# user_control_design_block.net
KiCad netlist of a schematic drawn in EAGLE
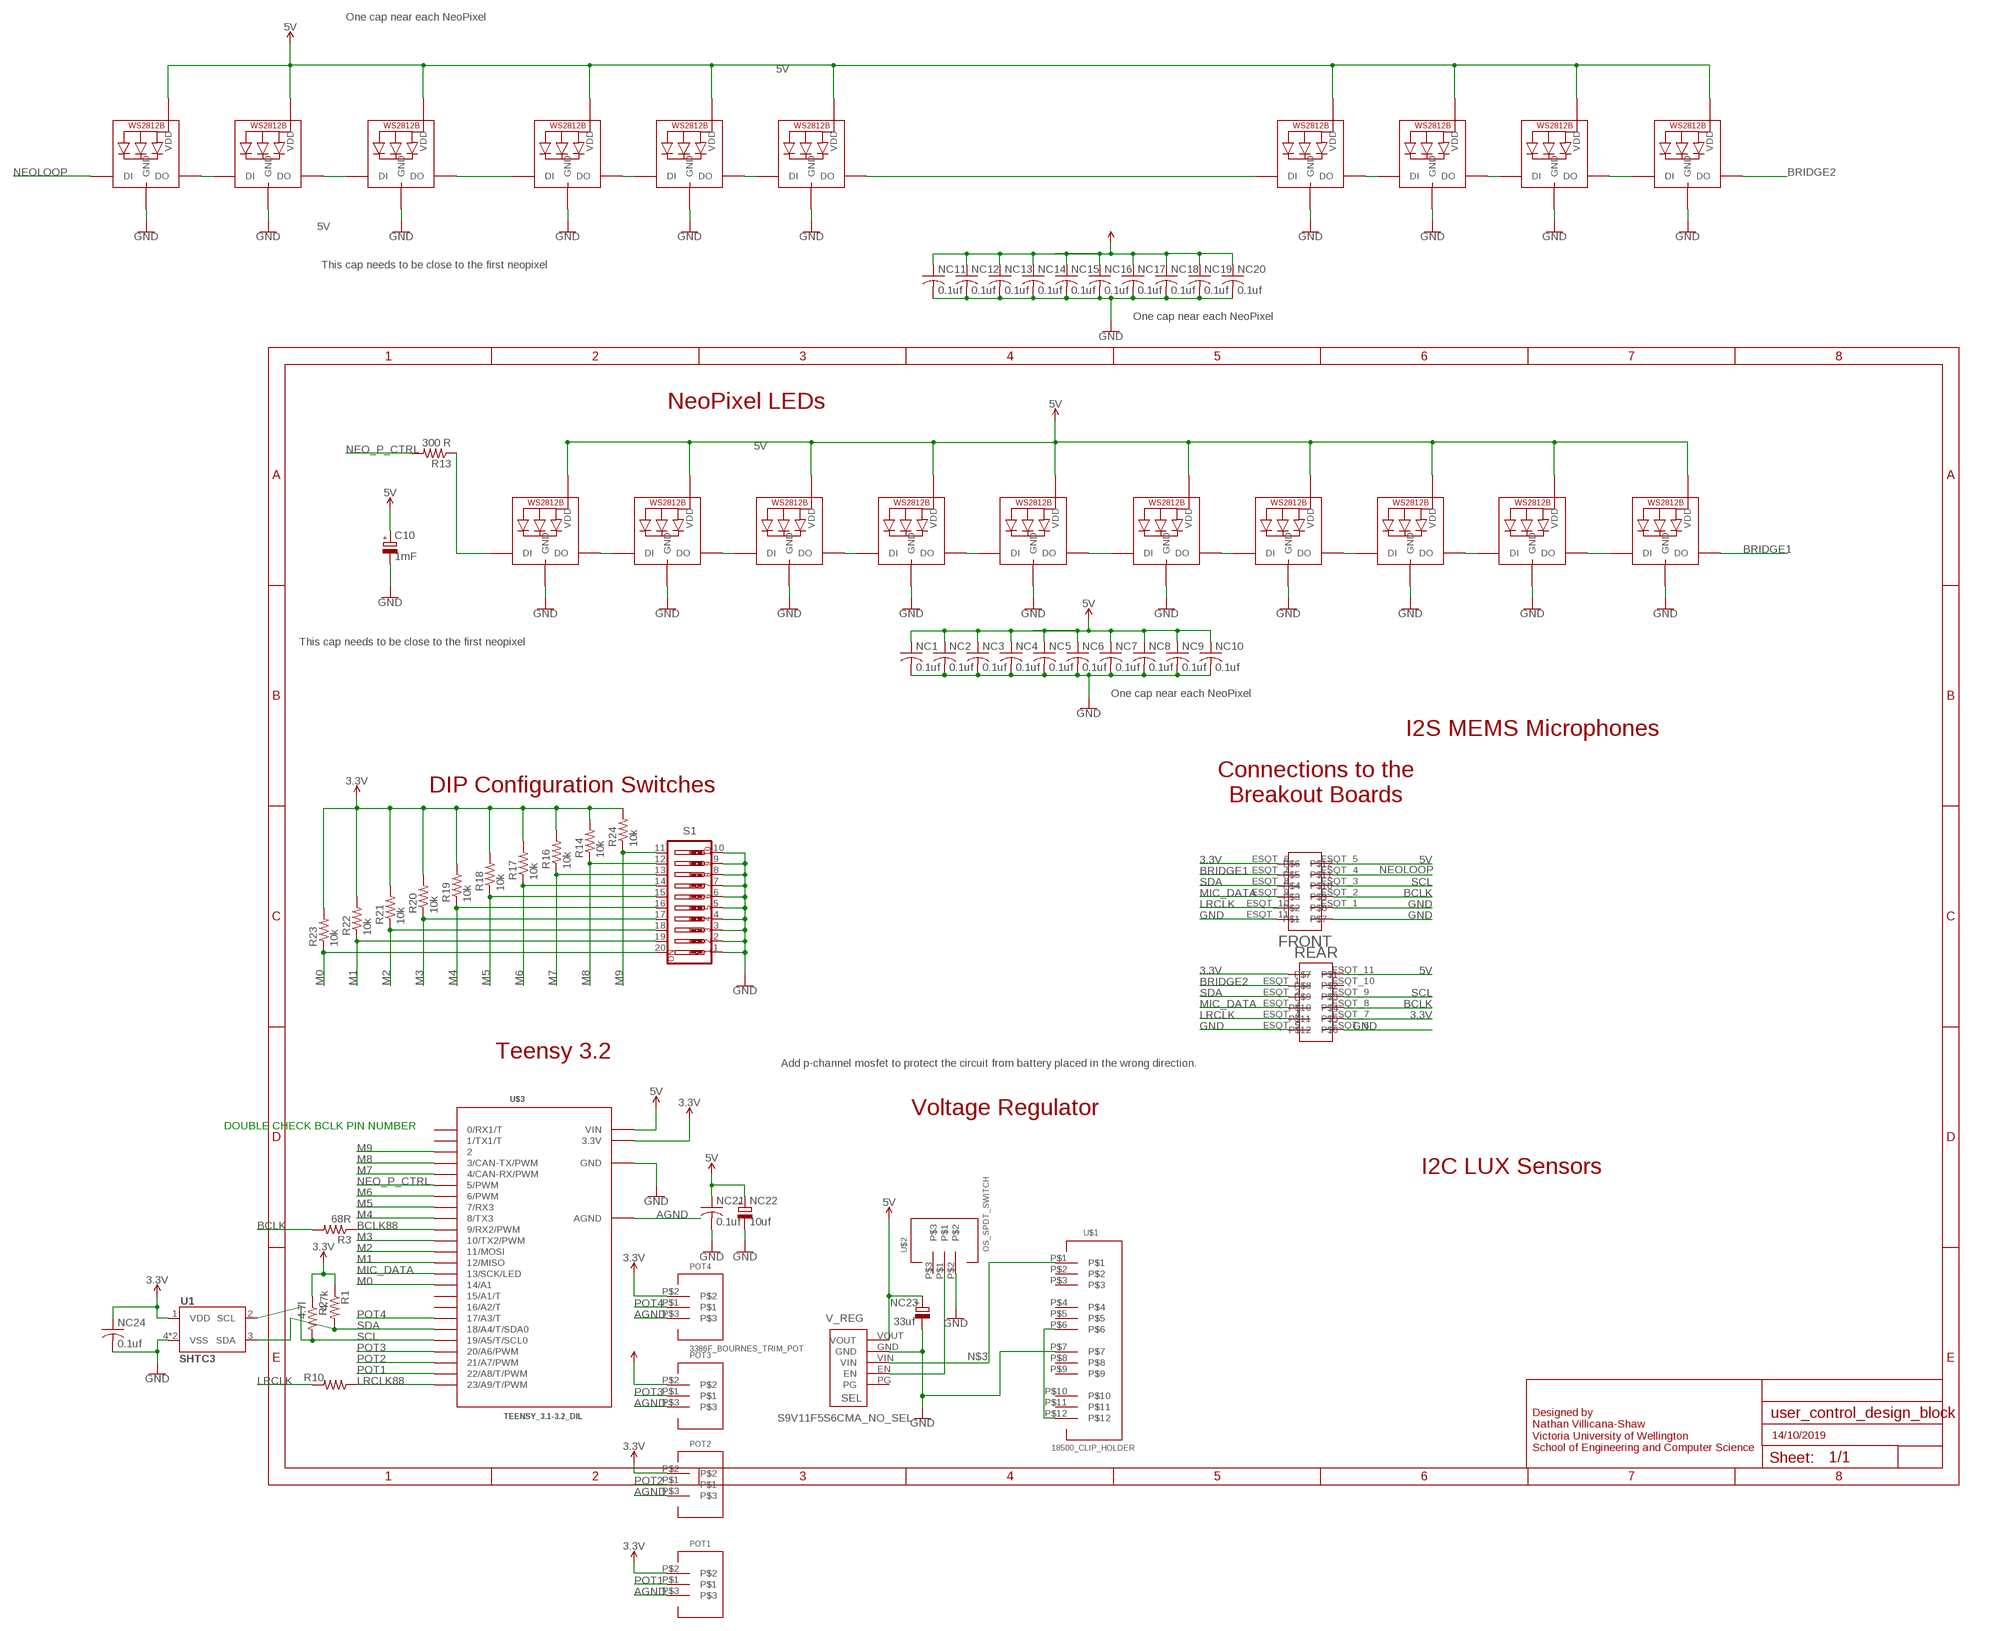
[diagram p0: schematic, sheet 1]

(export (version "E")
  (design (tool "Eeschema 10.0.6"))
  (components
    (comp (ref "C10")
      (value "1mF")
      (footprint "eagle-import:153CLV-1010")
      (libsource (lib "eagle-import") (part "CPOL-EU153CLV-1010"))
    )
    (comp (ref "FRONT")
      (value "SAMTEC_ESQT_2X6_THROUGH_HOLE")
      (footprint "eagle-import:SAMTEC_ESQT_2X6_THROUGH_HOLE")
      (libsource (lib "eagle-import") (part "SAMTEC_ESQT_2X6_THROUGH_HOLE"))
    )
    (comp (ref "NC1")
      (value "0.1uf")
      (footprint "eagle-import:C0805K")
      (libsource (lib "eagle-import") (part "C-USC0805K"))
    )
    (comp (ref "NC2")
      (value "0.1uf")
      (footprint "eagle-import:C0805K")
      (libsource (lib "eagle-import") (part "C-USC0805K"))
    )
    (comp (ref "NC3")
      (value "0.1uf")
      (footprint "eagle-import:C0805K")
      (libsource (lib "eagle-import") (part "C-USC0805K"))
    )
    (comp (ref "NC4")
      (value "0.1uf")
      (footprint "eagle-import:C0805K")
      (libsource (lib "eagle-import") (part "C-USC0805K"))
    )
    (comp (ref "NC5")
      (value "0.1uf")
      (footprint "eagle-import:C0805K")
      (libsource (lib "eagle-import") (part "C-USC0805K"))
    )
    (comp (ref "NC6")
      (value "0.1uf")
      (footprint "eagle-import:C0805K")
      (libsource (lib "eagle-import") (part "C-USC0805K"))
    )
    (comp (ref "NC7")
      (value "0.1uf")
      (footprint "eagle-import:C0805K")
      (libsource (lib "eagle-import") (part "C-USC0805K"))
    )
    (comp (ref "NC8")
      (value "0.1uf")
      (footprint "eagle-import:C0805K")
      (libsource (lib "eagle-import") (part "C-USC0805K"))
    )
    (comp (ref "NC9")
      (value "0.1uf")
      (footprint "eagle-import:C0805K")
      (libsource (lib "eagle-import") (part "C-USC0805K"))
    )
    (comp (ref "NC10")
      (value "0.1uf")
      (footprint "eagle-import:C0805K")
      (libsource (lib "eagle-import") (part "C-USC0805K"))
    )
    (comp (ref "NC11")
      (value "0.1uf")
      (footprint "eagle-import:C0805K")
      (libsource (lib "eagle-import") (part "C-USC0805K"))
    )
    (comp (ref "NC12")
      (value "0.1uf")
      (footprint "eagle-import:C0805K")
      (libsource (lib "eagle-import") (part "C-USC0805K"))
    )
    (comp (ref "NC13")
      (value "0.1uf")
      (footprint "eagle-import:C0805K")
      (libsource (lib "eagle-import") (part "C-USC0805K"))
    )
    (comp (ref "NC14")
      (value "0.1uf")
      (footprint "eagle-import:C0805K")
      (libsource (lib "eagle-import") (part "C-USC0805K"))
    )
    (comp (ref "NC15")
      (value "0.1uf")
      (footprint "eagle-import:C0805K")
      (libsource (lib "eagle-import") (part "C-USC0805K"))
    )
    (comp (ref "NC16")
      (value "0.1uf")
      (footprint "eagle-import:C0805K")
      (libsource (lib "eagle-import") (part "C-USC0805K"))
    )
    (comp (ref "NC17")
      (value "0.1uf")
      (footprint "eagle-import:C0805K")
      (libsource (lib "eagle-import") (part "C-USC0805K"))
    )
    (comp (ref "NC18")
      (value "0.1uf")
      (footprint "eagle-import:C0805K")
      (libsource (lib "eagle-import") (part "C-USC0805K"))
    )
    (comp (ref "NC19")
      (value "0.1uf")
      (footprint "eagle-import:C0805K")
      (libsource (lib "eagle-import") (part "C-USC0805K"))
    )
    (comp (ref "NC20")
      (value "0.1uf")
      (footprint "eagle-import:C0805K")
      (libsource (lib "eagle-import") (part "C-USC0805K"))
    )
    (comp (ref "NC21")
      (value "0.1uf")
      (footprint "eagle-import:C0805K")
      (libsource (lib "eagle-import") (part "C-USC0805K"))
    )
    (comp (ref "NC22")
      (value "10uf")
      (footprint "eagle-import:E2,5-7")
      (libsource (lib "eagle-import") (part "CPOL-EUE2.5-7"))
    )
    (comp (ref "NC23")
      (value "33uf")
      (footprint "eagle-import:E2,5-7")
      (libsource (lib "eagle-import") (part "CPOL-EUE2.5-7"))
    )
    (comp (ref "NC24")
      (value "0.1uf")
      (footprint "eagle-import:C0805K")
      (libsource (lib "eagle-import") (part "C-USC0805K"))
    )
    (comp (ref "NEO1")
      (value "WS2812B5050")
      (footprint "eagle-import:WS2812B")
      (libsource (lib "eagle-import") (part "WS2812B5050"))
    )
    (comp (ref "NEO2")
      (value "WS2812B5050")
      (footprint "eagle-import:WS2812B")
      (libsource (lib "eagle-import") (part "WS2812B5050"))
    )
    (comp (ref "NEO3")
      (value "WS2812B5050")
      (footprint "eagle-import:WS2812B")
      (libsource (lib "eagle-import") (part "WS2812B5050"))
    )
    (comp (ref "NEO4")
      (value "WS2812B5050")
      (footprint "eagle-import:WS2812B")
      (libsource (lib "eagle-import") (part "WS2812B5050"))
    )
    (comp (ref "NEO5")
      (value "WS2812B5050")
      (footprint "eagle-import:WS2812B")
      (libsource (lib "eagle-import") (part "WS2812B5050"))
    )
    (comp (ref "NEO6")
      (value "WS2812B5050")
      (footprint "eagle-import:WS2812B")
      (libsource (lib "eagle-import") (part "WS2812B5050"))
    )
    (comp (ref "NEO7")
      (value "WS2812B5050")
      (footprint "eagle-import:WS2812B")
      (libsource (lib "eagle-import") (part "WS2812B5050"))
    )
    (comp (ref "NEO8")
      (value "WS2812B5050")
      (footprint "eagle-import:WS2812B")
      (libsource (lib "eagle-import") (part "WS2812B5050"))
    )
    (comp (ref "NEO9")
      (value "WS2812B5050")
      (footprint "eagle-import:WS2812B")
      (libsource (lib "eagle-import") (part "WS2812B5050"))
    )
    (comp (ref "NEO10")
      (value "WS2812B5050")
      (footprint "eagle-import:WS2812B")
      (libsource (lib "eagle-import") (part "WS2812B5050"))
    )
    (comp (ref "NEO11")
      (value "WS2812B5050")
      (footprint "eagle-import:WS2812B")
      (libsource (lib "eagle-import") (part "WS2812B5050"))
    )
    (comp (ref "NEO12")
      (value "WS2812B5050")
      (footprint "eagle-import:WS2812B")
      (libsource (lib "eagle-import") (part "WS2812B5050"))
    )
    (comp (ref "NEO13")
      (value "WS2812B5050")
      (footprint "eagle-import:WS2812B")
      (libsource (lib "eagle-import") (part "WS2812B5050"))
    )
    (comp (ref "NEO14")
      (value "WS2812B5050")
      (footprint "eagle-import:WS2812B")
      (libsource (lib "eagle-import") (part "WS2812B5050"))
    )
    (comp (ref "NEO15")
      (value "WS2812B5050")
      (footprint "eagle-import:WS2812B")
      (libsource (lib "eagle-import") (part "WS2812B5050"))
    )
    (comp (ref "NEO16")
      (value "WS2812B5050")
      (footprint "eagle-import:WS2812B")
      (libsource (lib "eagle-import") (part "WS2812B5050"))
    )
    (comp (ref "NEO17")
      (value "WS2812B5050")
      (footprint "eagle-import:WS2812B")
      (libsource (lib "eagle-import") (part "WS2812B5050"))
    )
    (comp (ref "NEO18")
      (value "WS2812B5050")
      (footprint "eagle-import:WS2812B")
      (libsource (lib "eagle-import") (part "WS2812B5050"))
    )
    (comp (ref "NEO19")
      (value "WS2812B5050")
      (footprint "eagle-import:WS2812B")
      (libsource (lib "eagle-import") (part "WS2812B5050"))
    )
    (comp (ref "NEO20")
      (value "WS2812B5050")
      (footprint "eagle-import:WS2812B")
      (libsource (lib "eagle-import") (part "WS2812B5050"))
    )
    (comp (ref "POT1")
      (value "3386F_BOURNES_TRIM_POT")
      (footprint "eagle-import:3386_BOURNS_TRIM_POT")
      (libsource (lib "eagle-import") (part "3386F_BOURNES_TRIM_POT"))
    )
    (comp (ref "POT2")
      (value "3386F_BOURNES_TRIM_POT")
      (footprint "eagle-import:3386_BOURNS_TRIM_POT")
      (libsource (lib "eagle-import") (part "3386F_BOURNES_TRIM_POT"))
    )
    (comp (ref "POT3")
      (value "3386F_BOURNES_TRIM_POT")
      (footprint "eagle-import:3386_BOURNS_TRIM_POT")
      (libsource (lib "eagle-import") (part "3386F_BOURNES_TRIM_POT"))
    )
    (comp (ref "POT4")
      (value "3386F_BOURNES_TRIM_POT")
      (footprint "eagle-import:3386_BOURNS_TRIM_POT")
      (libsource (lib "eagle-import") (part "3386F_BOURNES_TRIM_POT"))
    )
    (comp (ref "R1")
      (value "4.7k")
      (footprint "eagle-import:R0805")
      (libsource (lib "eagle-import") (part "R-US_R0805"))
    )
    (comp (ref "R2")
      (value "4.7l")
      (footprint "eagle-import:R0805")
      (libsource (lib "eagle-import") (part "R-US_R0805"))
    )
    (comp (ref "R3")
      (value "68R")
      (footprint "eagle-import:R0805")
      (libsource (lib "eagle-import") (part "R-US_R0805"))
    )
    (comp (ref "R10")
      (value "68R")
      (footprint "eagle-import:R0805")
      (libsource (lib "eagle-import") (part "R-US_R0805"))
    )
    (comp (ref "R13")
      (value "300 R")
      (footprint "eagle-import:R0805")
      (libsource (lib "eagle-import") (part "R-US_R0805"))
    )
    (comp (ref "R14")
      (value "10k")
      (footprint "eagle-import:R0805")
      (libsource (lib "eagle-import") (part "R-US_R0805"))
    )
    (comp (ref "R16")
      (value "10k")
      (footprint "eagle-import:R0805")
      (libsource (lib "eagle-import") (part "R-US_R0805"))
    )
    (comp (ref "R17")
      (value "10k")
      (footprint "eagle-import:R0805")
      (libsource (lib "eagle-import") (part "R-US_R0805"))
    )
    (comp (ref "R18")
      (value "10k")
      (footprint "eagle-import:R0805")
      (libsource (lib "eagle-import") (part "R-US_R0805"))
    )
    (comp (ref "R19")
      (value "10k")
      (footprint "eagle-import:R0805")
      (libsource (lib "eagle-import") (part "R-US_R0805"))
    )
    (comp (ref "R20")
      (value "10k")
      (footprint "eagle-import:R0805")
      (libsource (lib "eagle-import") (part "R-US_R0805"))
    )
    (comp (ref "R21")
      (value "10k")
      (footprint "eagle-import:R0805")
      (libsource (lib "eagle-import") (part "R-US_R0805"))
    )
    (comp (ref "R22")
      (value "10k")
      (footprint "eagle-import:R0805")
      (libsource (lib "eagle-import") (part "R-US_R0805"))
    )
    (comp (ref "R23")
      (value "10k")
      (footprint "eagle-import:M0805")
      (libsource (lib "eagle-import") (part "R-US_M0805"))
    )
    (comp (ref "R24")
      (value "10k")
      (footprint "eagle-import:R0805")
      (libsource (lib "eagle-import") (part "R-US_R0805"))
    )
    (comp (ref "REAR")
      (value "SAMTEC_ESQT_2X6_THROUGH_HOLE")
      (footprint "eagle-import:SAMTEC_ESQT_2X6_THROUGH_HOLE")
      (libsource (lib "eagle-import") (part "SAMTEC_ESQT_2X6_THROUGH_HOLE"))
    )
    (comp (ref "S1")
      (value "SW_DIP-10")
      (footprint "eagle-import:EDG-10")
      (libsource (lib "eagle-import") (part "SW_DIP-10"))
    )
    (comp (ref "U$1")
      (value "18500_CLIP_HOLDER")
      (footprint "eagle-import:3PINBATTERY_CLIP")
      (fields (field (name "SPICEPREFIX") "X"))
      (libsource (lib "eagle-import") (part "18500_CLIP_HOLDER"))
    )
    (comp (ref "U$2")
      (value "OS_SPDT_SWITCH")
      (footprint "eagle-import:OS_SPDT_SLIDE_SWITCH")
      (libsource (lib "eagle-import") (part "OS_SPDT_SWITCH"))
    )
    (comp (ref "U$3")
      (value "TEENSY_3.1-3.2_DIL")
      (footprint "eagle-import:TEENSY_3.0-3.2&LC_DIL")
      (libsource (lib "eagle-import") (part "TEENSY_3.1-3.2_DIL"))
    )
    (comp (ref "U1")
      (value "SHTC3")
      (footprint "eagle-import:SHTC3")
      (libsource (lib "eagle-import") (part "SHTC3"))
    )
    (comp (ref "V_REG")
      (value "S9V11F5S6CMA_NO_SEL")
      (footprint "eagle-import:S9V11F3S5CMA_NO_SEL")
      (libsource (lib "eagle-import") (part "S9V11F5S6CMA_NO_SEL"))
    )
  )
  (nets
    (net (code "1") (name "/AGND") (class "Default")
      (node (ref "POT1") (pin "P$3") (pinfunction "P$3_P$3") (pintype "bidirectional"))
      (node (ref "POT2") (pin "P$3") (pinfunction "P$3_P$3") (pintype "bidirectional"))
      (node (ref "POT3") (pin "P$3") (pinfunction "P$3_P$3") (pintype "bidirectional"))
      (node (ref "POT4") (pin "P$3") (pinfunction "P$3_P$3") (pintype "bidirectional"))
      (node (ref "U$3") (pin "AGND") (pinfunction "AGND_AGND") (pintype "power_in"))
    )
    (net (code "2") (name "/BCLK") (class "Default")
      (node (ref "FRONT") (pin "ESQT_2") (pinfunction "P$3_ESQT_2") (pintype "bidirectional"))
      (node (ref "R3") (pin "2") (pinfunction "2_2") (pintype "passive"))
      (node (ref "REAR") (pin "ESQT_8") (pinfunction "P$10_ESQT_8") (pintype "bidirectional"))
    )
    (net (code "3") (name "/BCLK88") (class "Default")
      (node (ref "R3") (pin "1") (pinfunction "1_1") (pintype "passive"))
      (node (ref "U$3") (pin "9") (pinfunction "9/RX2/PWM_9") (pintype "bidirectional"))
    )
    (net (code "4") (name "/BRIDGE1") (class "Default")
      (node (ref "FRONT") (pin "ESQT_7") (pinfunction "P$11_ESQT_7") (pintype "bidirectional"))
      (node (ref "NEO10") (pin "2-DOUT") (pinfunction "DO_2-DOUT") (pintype "output"))
    )
    (net (code "5") (name "/BRIDGE2") (class "Default")
      (node (ref "NEO20") (pin "2-DOUT") (pinfunction "DO_2-DOUT") (pintype "output"))
      (node (ref "REAR") (pin "ESQT_1") (pinfunction "P$2_ESQT_1") (pintype "bidirectional"))
    )
    (net (code "6") (name "/LRCLK") (class "Default")
      (node (ref "FRONT") (pin "ESQT_10") (pinfunction "P$8_ESQT_10") (pintype "bidirectional"))
      (node (ref "R10") (pin "2") (pinfunction "2_2") (pintype "passive"))
      (node (ref "REAR") (pin "ESQT_4") (pinfunction "P$5_ESQT_4") (pintype "bidirectional"))
    )
    (net (code "7") (name "/LRCLK88") (class "Default")
      (node (ref "R10") (pin "1") (pinfunction "1_1") (pintype "passive"))
      (node (ref "U$3") (pin "23/A9") (pinfunction "23/A9/T/PWM_23/A9") (pintype "bidirectional"))
    )
    (net (code "8") (name "/M0") (class "Default")
      (node (ref "R23") (pin "1") (pinfunction "1_1") (pintype "passive"))
      (node (ref "S1") (pin "20") (pinfunction "20_20") (pintype "passive"))
      (node (ref "U$3") (pin "14/A0") (pinfunction "14/A1_14/A0") (pintype "bidirectional"))
    )
    (net (code "9") (name "/M1") (class "Default")
      (node (ref "R22") (pin "1") (pinfunction "1_1") (pintype "passive"))
      (node (ref "S1") (pin "19") (pinfunction "19_19") (pintype "passive"))
      (node (ref "U$3") (pin "12") (pinfunction "12/MISO_12") (pintype "bidirectional"))
    )
    (net (code "10") (name "/M2") (class "Default")
      (node (ref "R21") (pin "1") (pinfunction "1_1") (pintype "passive"))
      (node (ref "S1") (pin "18") (pinfunction "18_18") (pintype "passive"))
      (node (ref "U$3") (pin "11") (pinfunction "11/MOSI_11") (pintype "bidirectional"))
    )
    (net (code "11") (name "/M3") (class "Default")
      (node (ref "R20") (pin "1") (pinfunction "1_1") (pintype "passive"))
      (node (ref "S1") (pin "17") (pinfunction "17_17") (pintype "passive"))
      (node (ref "U$3") (pin "10") (pinfunction "10/TX2/PWM_10") (pintype "bidirectional"))
    )
    (net (code "12") (name "/M4") (class "Default")
      (node (ref "R19") (pin "1") (pinfunction "1_1") (pintype "passive"))
      (node (ref "S1") (pin "16") (pinfunction "16_16") (pintype "passive"))
      (node (ref "U$3") (pin "8") (pinfunction "8/TX3_8") (pintype "bidirectional"))
    )
    (net (code "13") (name "/M5") (class "Default")
      (node (ref "R18") (pin "1") (pinfunction "1_1") (pintype "passive"))
      (node (ref "S1") (pin "15") (pinfunction "15_15") (pintype "passive"))
      (node (ref "U$3") (pin "7") (pinfunction "7/RX3_7") (pintype "bidirectional"))
    )
    (net (code "14") (name "/M6") (class "Default")
      (node (ref "R17") (pin "1") (pinfunction "1_1") (pintype "passive"))
      (node (ref "S1") (pin "14") (pinfunction "14_14") (pintype "passive"))
      (node (ref "U$3") (pin "6") (pinfunction "6/PWM_6") (pintype "bidirectional"))
    )
    (net (code "15") (name "/M7") (class "Default")
      (node (ref "R16") (pin "1") (pinfunction "1_1") (pintype "passive"))
      (node (ref "S1") (pin "13") (pinfunction "13_13") (pintype "passive"))
      (node (ref "U$3") (pin "4") (pinfunction "4/CAN-RX/PWM_4") (pintype "bidirectional"))
    )
    (net (code "16") (name "/M8") (class "Default")
      (node (ref "R14") (pin "1") (pinfunction "1_1") (pintype "passive"))
      (node (ref "S1") (pin "12") (pinfunction "12_12") (pintype "passive"))
      (node (ref "U$3") (pin "3") (pinfunction "3/CAN-TX/PWM_3") (pintype "bidirectional"))
    )
    (net (code "17") (name "/M9") (class "Default")
      (node (ref "R24") (pin "1") (pinfunction "1_1") (pintype "passive"))
      (node (ref "S1") (pin "11") (pinfunction "11_11") (pintype "passive"))
      (node (ref "U$3") (pin "2") (pinfunction "2_2") (pintype "bidirectional"))
    )
    (net (code "18") (name "/MIC_DATA") (class "Default")
      (node (ref "FRONT") (pin "ESQT_9") (pinfunction "P$9_ESQT_9") (pintype "bidirectional"))
      (node (ref "REAR") (pin "ESQT_3") (pinfunction "P$4_ESQT_3") (pintype "bidirectional"))
      (node (ref "U$3") (pin "13") (pinfunction "13/SCK/LED_13") (pintype "bidirectional"))
    )
    (net (code "19") (name "/N$3") (class "Default")
      (node (ref "U$1") (pin "P$1") (pinfunction "P$1_P$1") (pintype "bidirectional"))
      (node (ref "V_REG") (pin "VIN") (pinfunction "VIN_VIN") (pintype "bidirectional"))
    )
    (net (code "20") (name "/NEOLOOP") (class "Default")
      (node (ref "FRONT") (pin "ESQT_4") (pinfunction "P$5_ESQT_4") (pintype "bidirectional"))
      (node (ref "NEO11") (pin "4-DIN") (pinfunction "DI_4-DIN") (pintype "input"))
    )
    (net (code "21") (name "/NEO_P_CTRL") (class "Default")
      (node (ref "R13") (pin "2") (pinfunction "2_2") (pintype "passive"))
      (node (ref "U$3") (pin "5") (pinfunction "5/PWM_5") (pintype "bidirectional"))
    )
    (net (code "22") (name "/POT1") (class "Default")
      (node (ref "POT1") (pin "P$1") (pinfunction "P$1_P$1") (pintype "bidirectional"))
      (node (ref "U$3") (pin "22/A8") (pinfunction "22/A8/T/PWM_22/A8") (pintype "bidirectional"))
    )
    (net (code "23") (name "/POT2") (class "Default")
      (node (ref "POT2") (pin "P$1") (pinfunction "P$1_P$1") (pintype "bidirectional"))
      (node (ref "U$3") (pin "21/A7") (pinfunction "21/A7/PWM_21/A7") (pintype "bidirectional"))
    )
    (net (code "24") (name "/POT3") (class "Default")
      (node (ref "POT3") (pin "P$1") (pinfunction "P$1_P$1") (pintype "bidirectional"))
      (node (ref "U$3") (pin "20/A6") (pinfunction "20/A6/PWM_20/A6") (pintype "bidirectional"))
    )
    (net (code "25") (name "/POT4") (class "Default")
      (node (ref "POT4") (pin "P$1") (pinfunction "P$1_P$1") (pintype "bidirectional"))
      (node (ref "U$3") (pin "17/A3") (pinfunction "17/A3/T_17/A3") (pintype "bidirectional"))
    )
    (net (code "26") (name "/SCL") (class "Default")
      (node (ref "FRONT") (pin "ESQT_3") (pinfunction "P$4_ESQT_3") (pintype "bidirectional"))
      (node (ref "R2") (pin "2") (pinfunction "2_2") (pintype "passive"))
      (node (ref "REAR") (pin "ESQT_9") (pinfunction "P$9_ESQT_9") (pintype "bidirectional"))
      (node (ref "U$3") (pin "19/A5") (pinfunction "19/A5/T/SCL0_19/A5") (pintype "bidirectional"))
      (node (ref "U1") (pin "2") (pinfunction "SCL_2") (pintype "bidirectional"))
    )
    (net (code "27") (name "/SDA") (class "Default")
      (node (ref "FRONT") (pin "ESQT_8") (pinfunction "P$10_ESQT_8") (pintype "bidirectional"))
      (node (ref "R1") (pin "2") (pinfunction "2_2") (pintype "passive"))
      (node (ref "REAR") (pin "ESQT_2") (pinfunction "P$3_ESQT_2") (pintype "bidirectional"))
      (node (ref "U$3") (pin "18/A4") (pinfunction "18/A4/T/SDA0_18/A4") (pintype "bidirectional"))
      (node (ref "U1") (pin "3") (pinfunction "SDA_3") (pintype "bidirectional"))
    )
    (net (code "28") (name "3.3V") (class "Default")
      (node (ref "FRONT") (pin "ESQT_6") (pinfunction "P$12_ESQT_6") (pintype "bidirectional"))
      (node (ref "NC24") (pin "1") (pinfunction "1_1") (pintype "passive"))
      (node (ref "POT1") (pin "P$2") (pinfunction "P$2_P$2") (pintype "bidirectional"))
      (node (ref "POT2") (pin "P$2") (pinfunction "P$2_P$2") (pintype "bidirectional"))
      (node (ref "POT3") (pin "P$2") (pinfunction "P$2_P$2") (pintype "bidirectional"))
      (node (ref "POT4") (pin "P$2") (pinfunction "P$2_P$2") (pintype "bidirectional"))
      (node (ref "R1") (pin "1") (pinfunction "1_1") (pintype "passive"))
      (node (ref "R14") (pin "2") (pinfunction "2_2") (pintype "passive"))
      (node (ref "R16") (pin "2") (pinfunction "2_2") (pintype "passive"))
      (node (ref "R17") (pin "2") (pinfunction "2_2") (pintype "passive"))
      (node (ref "R18") (pin "2") (pinfunction "2_2") (pintype "passive"))
      (node (ref "R19") (pin "2") (pinfunction "2_2") (pintype "passive"))
      (node (ref "R2") (pin "1") (pinfunction "1_1") (pintype "passive"))
      (node (ref "R20") (pin "2") (pinfunction "2_2") (pintype "passive"))
      (node (ref "R21") (pin "2") (pinfunction "2_2") (pintype "passive"))
      (node (ref "R22") (pin "2") (pinfunction "2_2") (pintype "passive"))
      (node (ref "R23") (pin "2") (pinfunction "2_2") (pintype "passive"))
      (node (ref "R24") (pin "2") (pinfunction "2_2") (pintype "passive"))
      (node (ref "REAR") (pin "ESQT_0") (pinfunction "P$1_ESQT_0") (pintype "bidirectional"))
      (node (ref "REAR") (pin "ESQT_7") (pinfunction "P$11_ESQT_7") (pintype "bidirectional"))
      (node (ref "U$3") (pin "3.3V") (pinfunction "3.3V_3.3V") (pintype "power_in"))
      (node (ref "U1") (pin "1") (pinfunction "VDD_1") (pintype "bidirectional"))
    )
    (net (code "29") (name "5V") (class "Default")
      (node (ref "C10") (pin "+") (pinfunction "+_+") (pintype "passive"))
      (node (ref "FRONT") (pin "ESQT_5") (pinfunction "P$6_ESQT_5") (pintype "bidirectional"))
      (node (ref "NC1") (pin "1") (pinfunction "1_1") (pintype "passive"))
      (node (ref "NC10") (pin "1") (pinfunction "1_1") (pintype "passive"))
      (node (ref "NC11") (pin "1") (pinfunction "1_1") (pintype "passive"))
      (node (ref "NC12") (pin "1") (pinfunction "1_1") (pintype "passive"))
      (node (ref "NC13") (pin "1") (pinfunction "1_1") (pintype "passive"))
      (node (ref "NC14") (pin "1") (pinfunction "1_1") (pintype "passive"))
      (node (ref "NC15") (pin "1") (pinfunction "1_1") (pintype "passive"))
      (node (ref "NC16") (pin "1") (pinfunction "1_1") (pintype "passive"))
      (node (ref "NC17") (pin "1") (pinfunction "1_1") (pintype "passive"))
      (node (ref "NC18") (pin "1") (pinfunction "1_1") (pintype "passive"))
      (node (ref "NC19") (pin "1") (pinfunction "1_1") (pintype "passive"))
      (node (ref "NC2") (pin "1") (pinfunction "1_1") (pintype "passive"))
      (node (ref "NC20") (pin "1") (pinfunction "1_1") (pintype "passive"))
      (node (ref "NC21") (pin "1") (pinfunction "1_1") (pintype "passive"))
      (node (ref "NC22") (pin "+") (pinfunction "+_+") (pintype "passive"))
      (node (ref "NC23") (pin "+") (pinfunction "+_+") (pintype "passive"))
      (node (ref "NC3") (pin "1") (pinfunction "1_1") (pintype "passive"))
      (node (ref "NC4") (pin "1") (pinfunction "1_1") (pintype "passive"))
      (node (ref "NC5") (pin "1") (pinfunction "1_1") (pintype "passive"))
      (node (ref "NC6") (pin "1") (pinfunction "1_1") (pintype "passive"))
      (node (ref "NC7") (pin "1") (pinfunction "1_1") (pintype "passive"))
      (node (ref "NC8") (pin "1") (pinfunction "1_1") (pintype "passive"))
      (node (ref "NC9") (pin "1") (pinfunction "1_1") (pintype "passive"))
      (node (ref "NEO1") (pin "1-VDD") (pinfunction "VDD_1-VDD") (pintype "power_in"))
      (node (ref "NEO10") (pin "1-VDD") (pinfunction "VDD_1-VDD") (pintype "power_in"))
      (node (ref "NEO11") (pin "1-VDD") (pinfunction "VDD_1-VDD") (pintype "power_in"))
      (node (ref "NEO12") (pin "1-VDD") (pinfunction "VDD_1-VDD") (pintype "power_in"))
      (node (ref "NEO13") (pin "1-VDD") (pinfunction "VDD_1-VDD") (pintype "power_in"))
      (node (ref "NEO14") (pin "1-VDD") (pinfunction "VDD_1-VDD") (pintype "power_in"))
      (node (ref "NEO15") (pin "1-VDD") (pinfunction "VDD_1-VDD") (pintype "power_in"))
      (node (ref "NEO16") (pin "1-VDD") (pinfunction "VDD_1-VDD") (pintype "power_in"))
      (node (ref "NEO17") (pin "1-VDD") (pinfunction "VDD_1-VDD") (pintype "power_in"))
      (node (ref "NEO18") (pin "1-VDD") (pinfunction "VDD_1-VDD") (pintype "power_in"))
      (node (ref "NEO19") (pin "1-VDD") (pinfunction "VDD_1-VDD") (pintype "power_in"))
      (node (ref "NEO2") (pin "1-VDD") (pinfunction "VDD_1-VDD") (pintype "power_in"))
      (node (ref "NEO20") (pin "1-VDD") (pinfunction "VDD_1-VDD") (pintype "power_in"))
      (node (ref "NEO3") (pin "1-VDD") (pinfunction "VDD_1-VDD") (pintype "power_in"))
      (node (ref "NEO4") (pin "1-VDD") (pinfunction "VDD_1-VDD") (pintype "power_in"))
      (node (ref "NEO5") (pin "1-VDD") (pinfunction "VDD_1-VDD") (pintype "power_in"))
      (node (ref "NEO6") (pin "1-VDD") (pinfunction "VDD_1-VDD") (pintype "power_in"))
      (node (ref "NEO7") (pin "1-VDD") (pinfunction "VDD_1-VDD") (pintype "power_in"))
      (node (ref "NEO8") (pin "1-VDD") (pinfunction "VDD_1-VDD") (pintype "power_in"))
      (node (ref "NEO9") (pin "1-VDD") (pinfunction "VDD_1-VDD") (pintype "power_in"))
      (node (ref "REAR") (pin "ESQT_11") (pinfunction "P$7_ESQT_11") (pintype "bidirectional"))
      (node (ref "U$3") (pin "VIN") (pinfunction "VIN_VIN") (pintype "power_in"))
      (node (ref "V_REG") (pin "VOUT") (pinfunction "VOUT_VOUT") (pintype "bidirectional"))
    )
    (net (code "30") (name "GND") (class "Default")
      (node (ref "C10") (pin "-") (pinfunction "-_-") (pintype "passive"))
      (node (ref "FRONT") (pin "ESQT_0") (pinfunction "P$1_ESQT_0") (pintype "bidirectional"))
      (node (ref "FRONT") (pin "ESQT_1") (pinfunction "P$2_ESQT_1") (pintype "bidirectional"))
      (node (ref "FRONT") (pin "ESQT_11") (pinfunction "P$7_ESQT_11") (pintype "bidirectional"))
      (node (ref "NC1") (pin "2") (pinfunction "2_2") (pintype "passive"))
      (node (ref "NC10") (pin "2") (pinfunction "2_2") (pintype "passive"))
      (node (ref "NC11") (pin "2") (pinfunction "2_2") (pintype "passive"))
      (node (ref "NC12") (pin "2") (pinfunction "2_2") (pintype "passive"))
      (node (ref "NC13") (pin "2") (pinfunction "2_2") (pintype "passive"))
      (node (ref "NC14") (pin "2") (pinfunction "2_2") (pintype "passive"))
      (node (ref "NC15") (pin "2") (pinfunction "2_2") (pintype "passive"))
      (node (ref "NC16") (pin "2") (pinfunction "2_2") (pintype "passive"))
      (node (ref "NC17") (pin "2") (pinfunction "2_2") (pintype "passive"))
      (node (ref "NC18") (pin "2") (pinfunction "2_2") (pintype "passive"))
      (node (ref "NC19") (pin "2") (pinfunction "2_2") (pintype "passive"))
      (node (ref "NC2") (pin "2") (pinfunction "2_2") (pintype "passive"))
      (node (ref "NC20") (pin "2") (pinfunction "2_2") (pintype "passive"))
      (node (ref "NC21") (pin "2") (pinfunction "2_2") (pintype "passive"))
      (node (ref "NC22") (pin "-") (pinfunction "-_-") (pintype "passive"))
      (node (ref "NC23") (pin "-") (pinfunction "-_-") (pintype "passive"))
      (node (ref "NC24") (pin "2") (pinfunction "2_2") (pintype "passive"))
      (node (ref "NC3") (pin "2") (pinfunction "2_2") (pintype "passive"))
      (node (ref "NC4") (pin "2") (pinfunction "2_2") (pintype "passive"))
      (node (ref "NC5") (pin "2") (pinfunction "2_2") (pintype "passive"))
      (node (ref "NC6") (pin "2") (pinfunction "2_2") (pintype "passive"))
      (node (ref "NC7") (pin "2") (pinfunction "2_2") (pintype "passive"))
      (node (ref "NC8") (pin "2") (pinfunction "2_2") (pintype "passive"))
      (node (ref "NC9") (pin "2") (pinfunction "2_2") (pintype "passive"))
      (node (ref "NEO1") (pin "3-GND") (pinfunction "GND_3-GND") (pintype "power_in"))
      (node (ref "NEO10") (pin "3-GND") (pinfunction "GND_3-GND") (pintype "power_in"))
      (node (ref "NEO11") (pin "3-GND") (pinfunction "GND_3-GND") (pintype "power_in"))
      (node (ref "NEO12") (pin "3-GND") (pinfunction "GND_3-GND") (pintype "power_in"))
      (node (ref "NEO13") (pin "3-GND") (pinfunction "GND_3-GND") (pintype "power_in"))
      (node (ref "NEO14") (pin "3-GND") (pinfunction "GND_3-GND") (pintype "power_in"))
      (node (ref "NEO15") (pin "3-GND") (pinfunction "GND_3-GND") (pintype "power_in"))
      (node (ref "NEO16") (pin "3-GND") (pinfunction "GND_3-GND") (pintype "power_in"))
      (node (ref "NEO17") (pin "3-GND") (pinfunction "GND_3-GND") (pintype "power_in"))
      (node (ref "NEO18") (pin "3-GND") (pinfunction "GND_3-GND") (pintype "power_in"))
      (node (ref "NEO19") (pin "3-GND") (pinfunction "GND_3-GND") (pintype "power_in"))
      (node (ref "NEO2") (pin "3-GND") (pinfunction "GND_3-GND") (pintype "power_in"))
      (node (ref "NEO20") (pin "3-GND") (pinfunction "GND_3-GND") (pintype "power_in"))
      (node (ref "NEO3") (pin "3-GND") (pinfunction "GND_3-GND") (pintype "power_in"))
      (node (ref "NEO4") (pin "3-GND") (pinfunction "GND_3-GND") (pintype "power_in"))
      (node (ref "NEO5") (pin "3-GND") (pinfunction "GND_3-GND") (pintype "power_in"))
      (node (ref "NEO6") (pin "3-GND") (pinfunction "GND_3-GND") (pintype "power_in"))
      (node (ref "NEO7") (pin "3-GND") (pinfunction "GND_3-GND") (pintype "power_in"))
      (node (ref "NEO8") (pin "3-GND") (pinfunction "GND_3-GND") (pintype "power_in"))
      (node (ref "NEO9") (pin "3-GND") (pinfunction "GND_3-GND") (pintype "power_in"))
      (node (ref "REAR") (pin "ESQT_5") (pinfunction "P$6_ESQT_5") (pintype "bidirectional"))
      (node (ref "REAR") (pin "ESQT_6") (pinfunction "P$12_ESQT_6") (pintype "bidirectional"))
      (node (ref "S1") (pin "1") (pinfunction "1_1") (pintype "passive"))
      (node (ref "S1") (pin "10") (pinfunction "10_10") (pintype "passive"))
      (node (ref "S1") (pin "2") (pinfunction "2_2") (pintype "passive"))
      (node (ref "S1") (pin "3") (pinfunction "3_3") (pintype "passive"))
      (node (ref "S1") (pin "4") (pinfunction "4_4") (pintype "passive"))
      (node (ref "S1") (pin "5") (pinfunction "5_5") (pintype "passive"))
      (node (ref "S1") (pin "6") (pinfunction "6_6") (pintype "passive"))
      (node (ref "S1") (pin "7") (pinfunction "7_7") (pintype "passive"))
      (node (ref "S1") (pin "8") (pinfunction "8_8") (pintype "passive"))
      (node (ref "S1") (pin "9") (pinfunction "9_9") (pintype "passive"))
      (node (ref "U$1") (pin "P$7") (pinfunction "P$7_P$7") (pintype "bidirectional"))
      (node (ref "U$2") (pin "P$2") (pinfunction "P$2_P$2") (pintype "bidirectional"))
      (node (ref "U$3") (pin "GND") (pinfunction "GND_GND") (pintype "power_in"))
      (node (ref "U1") (pin "4") (pinfunction "VSS_4") (pintype "bidirectional"))
      (node (ref "U1") (pin "5") (pinfunction "VSS_5") (pintype "bidirectional"))
      (node (ref "V_REG") (pin "GND") (pinfunction "GND_GND") (pintype "bidirectional"))
    )
    (net (code "31") (name "Net-(NEO1-DI)") (class "Default")
      (node (ref "NEO1") (pin "4-DIN") (pinfunction "DI_4-DIN") (pintype "input"))
      (node (ref "R13") (pin "1") (pinfunction "1_1") (pintype "passive"))
    )
    (net (code "32") (name "Net-(NEO1-DO)") (class "Default")
      (node (ref "NEO1") (pin "2-DOUT") (pinfunction "DO_2-DOUT") (pintype "output"))
      (node (ref "NEO2") (pin "4-DIN") (pinfunction "DI_4-DIN") (pintype "input"))
    )
    (net (code "33") (name "Net-(NEO2-DO)") (class "Default")
      (node (ref "NEO2") (pin "2-DOUT") (pinfunction "DO_2-DOUT") (pintype "output"))
      (node (ref "NEO3") (pin "4-DIN") (pinfunction "DI_4-DIN") (pintype "input"))
    )
    (net (code "34") (name "Net-(NEO3-DO)") (class "Default")
      (node (ref "NEO3") (pin "2-DOUT") (pinfunction "DO_2-DOUT") (pintype "output"))
      (node (ref "NEO4") (pin "4-DIN") (pinfunction "DI_4-DIN") (pintype "input"))
    )
    (net (code "35") (name "Net-(NEO4-DO)") (class "Default")
      (node (ref "NEO4") (pin "2-DOUT") (pinfunction "DO_2-DOUT") (pintype "output"))
      (node (ref "NEO5") (pin "4-DIN") (pinfunction "DI_4-DIN") (pintype "input"))
    )
    (net (code "36") (name "Net-(NEO5-DO)") (class "Default")
      (node (ref "NEO5") (pin "2-DOUT") (pinfunction "DO_2-DOUT") (pintype "output"))
      (node (ref "NEO6") (pin "4-DIN") (pinfunction "DI_4-DIN") (pintype "input"))
    )
    (net (code "37") (name "Net-(NEO6-DO)") (class "Default")
      (node (ref "NEO6") (pin "2-DOUT") (pinfunction "DO_2-DOUT") (pintype "output"))
      (node (ref "NEO7") (pin "4-DIN") (pinfunction "DI_4-DIN") (pintype "input"))
    )
    (net (code "38") (name "Net-(NEO7-DO)") (class "Default")
      (node (ref "NEO7") (pin "2-DOUT") (pinfunction "DO_2-DOUT") (pintype "output"))
      (node (ref "NEO8") (pin "4-DIN") (pinfunction "DI_4-DIN") (pintype "input"))
    )
    (net (code "39") (name "Net-(NEO8-DO)") (class "Default")
      (node (ref "NEO8") (pin "2-DOUT") (pinfunction "DO_2-DOUT") (pintype "output"))
      (node (ref "NEO9") (pin "4-DIN") (pinfunction "DI_4-DIN") (pintype "input"))
    )
    (net (code "40") (name "Net-(NEO10-DI)") (class "Default")
      (node (ref "NEO10") (pin "4-DIN") (pinfunction "DI_4-DIN") (pintype "input"))
      (node (ref "NEO9") (pin "2-DOUT") (pinfunction "DO_2-DOUT") (pintype "output"))
    )
    (net (code "41") (name "Net-(NEO11-DO)") (class "Default")
      (node (ref "NEO11") (pin "2-DOUT") (pinfunction "DO_2-DOUT") (pintype "output"))
      (node (ref "NEO12") (pin "4-DIN") (pinfunction "DI_4-DIN") (pintype "input"))
    )
    (net (code "42") (name "Net-(NEO12-DO)") (class "Default")
      (node (ref "NEO12") (pin "2-DOUT") (pinfunction "DO_2-DOUT") (pintype "output"))
      (node (ref "NEO13") (pin "4-DIN") (pinfunction "DI_4-DIN") (pintype "input"))
    )
    (net (code "43") (name "Net-(NEO13-DO)") (class "Default")
      (node (ref "NEO13") (pin "2-DOUT") (pinfunction "DO_2-DOUT") (pintype "output"))
      (node (ref "NEO14") (pin "4-DIN") (pinfunction "DI_4-DIN") (pintype "input"))
    )
    (net (code "44") (name "Net-(NEO14-DO)") (class "Default")
      (node (ref "NEO14") (pin "2-DOUT") (pinfunction "DO_2-DOUT") (pintype "output"))
      (node (ref "NEO15") (pin "4-DIN") (pinfunction "DI_4-DIN") (pintype "input"))
    )
    (net (code "45") (name "Net-(NEO15-DO)") (class "Default")
      (node (ref "NEO15") (pin "2-DOUT") (pinfunction "DO_2-DOUT") (pintype "output"))
      (node (ref "NEO16") (pin "4-DIN") (pinfunction "DI_4-DIN") (pintype "input"))
    )
    (net (code "46") (name "Net-(NEO16-DO)") (class "Default")
      (node (ref "NEO16") (pin "2-DOUT") (pinfunction "DO_2-DOUT") (pintype "output"))
      (node (ref "NEO17") (pin "4-DIN") (pinfunction "DI_4-DIN") (pintype "input"))
    )
    (net (code "47") (name "Net-(NEO17-DO)") (class "Default")
      (node (ref "NEO17") (pin "2-DOUT") (pinfunction "DO_2-DOUT") (pintype "output"))
      (node (ref "NEO18") (pin "4-DIN") (pinfunction "DI_4-DIN") (pintype "input"))
    )
    (net (code "48") (name "Net-(NEO18-DO)") (class "Default")
      (node (ref "NEO18") (pin "2-DOUT") (pinfunction "DO_2-DOUT") (pintype "output"))
      (node (ref "NEO19") (pin "4-DIN") (pinfunction "DI_4-DIN") (pintype "input"))
    )
    (net (code "49") (name "Net-(NEO19-DO)") (class "Default")
      (node (ref "NEO19") (pin "2-DOUT") (pinfunction "DO_2-DOUT") (pintype "output"))
      (node (ref "NEO20") (pin "4-DIN") (pinfunction "DI_4-DIN") (pintype "input"))
    )
    (net (code "50") (name "Net-(U$1-PadP$12)") (class "Default")
      (node (ref "U$1") (pin "P$12") (pinfunction "P$12_P$12") (pintype "bidirectional"))
      (node (ref "U$1") (pin "P$6") (pinfunction "P$6_P$6") (pintype "bidirectional"))
    )
    (net (code "51") (name "Net-(U$2-PadP$1)") (class "Default")
      (node (ref "U$2") (pin "P$1") (pinfunction "P$1_P$1") (pintype "bidirectional"))
      (node (ref "V_REG") (pin "EN") (pinfunction "EN_EN") (pintype "bidirectional"))
    )
    (net (code "52") (name "unconnected-(REAR-P$8-PadESQT_10)") (class "Default")
      (node (ref "REAR") (pin "ESQT_10") (pinfunction "P$8_ESQT_10") (pintype "bidirectional"))
    )
    (net (code "53") (name "unconnected-(U$1-PadP$2)") (class "Default")
      (node (ref "U$1") (pin "P$2") (pinfunction "P$2_P$2") (pintype "bidirectional"))
    )
    (net (code "54") (name "unconnected-(U$1-PadP$3)") (class "Default")
      (node (ref "U$1") (pin "P$3") (pinfunction "P$3_P$3") (pintype "bidirectional"))
    )
    (net (code "55") (name "unconnected-(U$1-PadP$4)") (class "Default")
      (node (ref "U$1") (pin "P$4") (pinfunction "P$4_P$4") (pintype "bidirectional"))
    )
    (net (code "56") (name "unconnected-(U$1-PadP$5)") (class "Default")
      (node (ref "U$1") (pin "P$5") (pinfunction "P$5_P$5") (pintype "bidirectional"))
    )
    (net (code "57") (name "unconnected-(U$1-PadP$8)") (class "Default")
      (node (ref "U$1") (pin "P$8") (pinfunction "P$8_P$8") (pintype "bidirectional"))
    )
    (net (code "58") (name "unconnected-(U$1-PadP$9)") (class "Default")
      (node (ref "U$1") (pin "P$9") (pinfunction "P$9_P$9") (pintype "bidirectional"))
    )
    (net (code "59") (name "unconnected-(U$1-PadP$10)") (class "Default")
      (node (ref "U$1") (pin "P$10") (pinfunction "P$10_P$10") (pintype "bidirectional"))
    )
    (net (code "60") (name "unconnected-(U$1-PadP$11)") (class "Default")
      (node (ref "U$1") (pin "P$11") (pinfunction "P$11_P$11") (pintype "bidirectional"))
    )
    (net (code "61") (name "unconnected-(U$2-PadP$3)") (class "Default")
      (node (ref "U$2") (pin "P$3") (pinfunction "P$3_P$3") (pintype "bidirectional"))
    )
    (net (code "62") (name "unconnected-(U$3-0{slash}RX1{slash}T-Pad0)") (class "Default")
      (node (ref "U$3") (pin "0") (pinfunction "0/RX1/T_0") (pintype "bidirectional"))
    )
    (net (code "63") (name "unconnected-(U$3-1{slash}TX1{slash}T-Pad1)") (class "Default")
      (node (ref "U$3") (pin "1") (pinfunction "1/TX1/T_1") (pintype "bidirectional"))
    )
    (net (code "64") (name "unconnected-(U$3-15{slash}A1{slash}T-Pad15{slash}A1)") (class "Default")
      (node (ref "U$3") (pin "15/A1") (pinfunction "15/A1/T_15/A1") (pintype "bidirectional"))
    )
    (net (code "65") (name "unconnected-(U$3-16{slash}A2{slash}T-Pad16{slash}A2)") (class "Default")
      (node (ref "U$3") (pin "16/A2") (pinfunction "16/A2/T_16/A2") (pintype "bidirectional"))
    )
    (net (code "66") (name "unconnected-(V_REG-PadPG)") (class "Default")
      (node (ref "V_REG") (pin "PG") (pinfunction "PG_PG") (pintype "bidirectional"))
    )
  )
)
